# CURRENT_SOURCE.net
KiCad netlist of a schematic drawn in Altium Designer
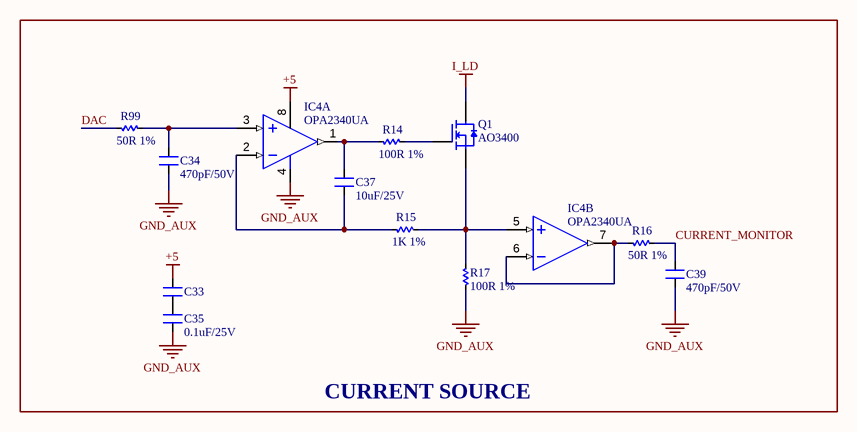
[diagram p0: CURRENT_SOURCE.SchDoc]

(export (version "E")
  (design (tool "Eeschema 10.0.6"))
  (components
    (comp (ref "C33")
      (value "0.1uF/25V")
      (footprint "SM-0603")
      (description "0603")
      (libsource (lib "Capacitors") (part "CM"))
    )
    (comp (ref "C34")
      (value "470pF/50V")
      (footprint "SM-0603")
      (description "0603")
      (libsource (lib "Capacitors") (part "CM"))
    )
    (comp (ref "C35")
      (value "0.1uF/25V")
      (footprint "SM-0603")
      (description "0603")
      (libsource (lib "Capacitors") (part "CM"))
    )
    (comp (ref "C37")
      (value "10uF/25V")
      (footprint "SM-0603")
      (description "0603")
      (libsource (lib "Capacitors") (part "CM"))
    )
    (comp (ref "C39")
      (value "470pF/50V")
      (footprint "SM-0603")
      (description "0603")
      (libsource (lib "Capacitors") (part "CM"))
    )
    (comp (ref "IC4")
      (value "OPA2340UA")
      (footprint "SO8")
      (description "8SOIC")
      (libsource (lib "Library") (part "LM358"))
    )
    (comp (ref "Q1") (value "AO3400") (footprint "SOT23-132") (libsource (lib "Library") (part "FET-N")))
    (comp (ref "R14")
      (value "100R 1%")
      (footprint "RES-SMD-0603")
      (description "0603")
      (fields
        (field (name "MANUFACTURER") "Generic Components")
        (field (name "PUBLISHER") "Altium Hobart Technology Centre")
      )
      (libsource (lib "Library") (part "Res-SMD"))
    )
    (comp (ref "R15")
      (value "1K 1%")
      (footprint "RES-SMD-0603")
      (description "0603")
      (fields
        (field (name "MANUFACTURER") "Generic Components")
        (field (name "PUBLISHER") "Altium Hobart Technology Centre")
      )
      (libsource (lib "Library") (part "Res-SMD"))
    )
    (comp (ref "R16")
      (value "50R 1%")
      (footprint "RES-SMD-0603")
      (description "0603")
      (fields
        (field (name "MANUFACTURER") "Generic Components")
        (field (name "PUBLISHER") "Altium Hobart Technology Centre")
      )
      (libsource (lib "Library") (part "Res-SMD"))
    )
    (comp (ref "R17")
      (value "100R 1%")
      (footprint "RES-SMD-0603")
      (description "0603")
      (fields
        (field (name "MANUFACTURER") "Generic Components")
        (field (name "PUBLISHER") "Altium Hobart Technology Centre")
      )
      (libsource (lib "Library") (part "Res-SMD"))
    )
    (comp (ref "R99")
      (value "50R 1%")
      (footprint "RES-SMD-0603")
      (description "0603")
      (fields
        (field (name "MANUFACTURER") "Generic Components")
        (field (name "PUBLISHER") "Altium Hobart Technology Centre")
      )
      (libsource (lib "Library") (part "Res-SMD"))
    )
  )
  (nets
    (net (code "1") (name "+5") (class "Default")
      (node (ref "C33") (pin "2") (pinfunction "2_2") (pintype "passive"))
      (node (ref "IC4") (pin "8") (pinfunction "+V_8") (pintype "passive"))
    )
    (net (code "2") (name "/CURRENT_MONITOR") (class "Default")
      (node (ref "C39") (pin "2") (pinfunction "2_2") (pintype "passive"))
      (node (ref "R16") (pin "2") (pinfunction "2_2") (pintype "passive"))
    )
    (net (code "3") (name "/DAC") (class "Default")
      (node (ref "R99") (pin "1") (pinfunction "1_1") (pintype "passive"))
    )
    (net (code "4") (name "GND_AUX") (class "Default")
      (node (ref "C34") (pin "1") (pinfunction "1_1") (pintype "passive"))
      (node (ref "C35") (pin "1") (pinfunction "1_1") (pintype "passive"))
      (node (ref "C39") (pin "1") (pinfunction "1_1") (pintype "passive"))
      (node (ref "IC4") (pin "4") (pinfunction "-V_4") (pintype "passive"))
      (node (ref "R17") (pin "1") (pinfunction "1_1") (pintype "passive"))
    )
    (net (code "5") (name "I_LD") (class "Default") (node (ref "Q1") (pin "3") (pintype "power_in")))
    (net (code "6") (name "Net-(C33-Pad1)") (class "Default")
      (node (ref "C33") (pin "1") (pinfunction "1_1") (pintype "passive"))
      (node (ref "C35") (pin "2") (pinfunction "2_2") (pintype "passive"))
    )
    (net (code "7") (name "Net-(IC4A-IN+)") (class "Default")
      (node (ref "C34") (pin "2") (pinfunction "2_2") (pintype "passive"))
      (node (ref "IC4") (pin "3") (pinfunction "IN+_3") (pintype "input"))
      (node (ref "R99") (pin "2") (pinfunction "2_2") (pintype "passive"))
    )
    (net (code "8") (name "Net-(IC4A-IN-)") (class "Default")
      (node (ref "C37") (pin "1") (pinfunction "1_1") (pintype "passive"))
      (node (ref "IC4") (pin "2") (pinfunction "IN-_2") (pintype "input"))
      (node (ref "R15") (pin "1") (pinfunction "1_1") (pintype "passive"))
    )
    (net (code "9") (name "Net-(IC4A-OUT)") (class "Default")
      (node (ref "C37") (pin "2") (pinfunction "2_2") (pintype "passive"))
      (node (ref "IC4") (pin "1") (pinfunction "OUT_1") (pintype "output"))
      (node (ref "R14") (pin "1") (pinfunction "1_1") (pintype "passive"))
    )
    (net (code "10") (name "Net-(IC4B-IN+)") (class "Default")
      (node (ref "IC4") (pin "5") (pinfunction "IN+_5") (pintype "input"))
      (node (ref "Q1") (pin "2") (pintype "power_in"))
      (node (ref "R15") (pin "2") (pinfunction "2_2") (pintype "passive"))
      (node (ref "R17") (pin "2") (pinfunction "2_2") (pintype "passive"))
    )
    (net (code "11") (name "Net-(IC4B-IN-)") (class "Default")
      (node (ref "IC4") (pin "6") (pinfunction "IN-_6") (pintype "input"))
      (node (ref "IC4") (pin "7") (pinfunction "OUT_7") (pintype "output"))
      (node (ref "R16") (pin "1") (pinfunction "1_1") (pintype "passive"))
    )
    (net (code "12") (name "Net-(Q1-Pad1)") (class "Default")
      (node (ref "Q1") (pin "1") (pintype "power_in"))
      (node (ref "R14") (pin "2") (pinfunction "2_2") (pintype "passive"))
    )
  )
)
